# SWITCHER_V2.net
KiCad netlist of a schematic drawn in EAGLE
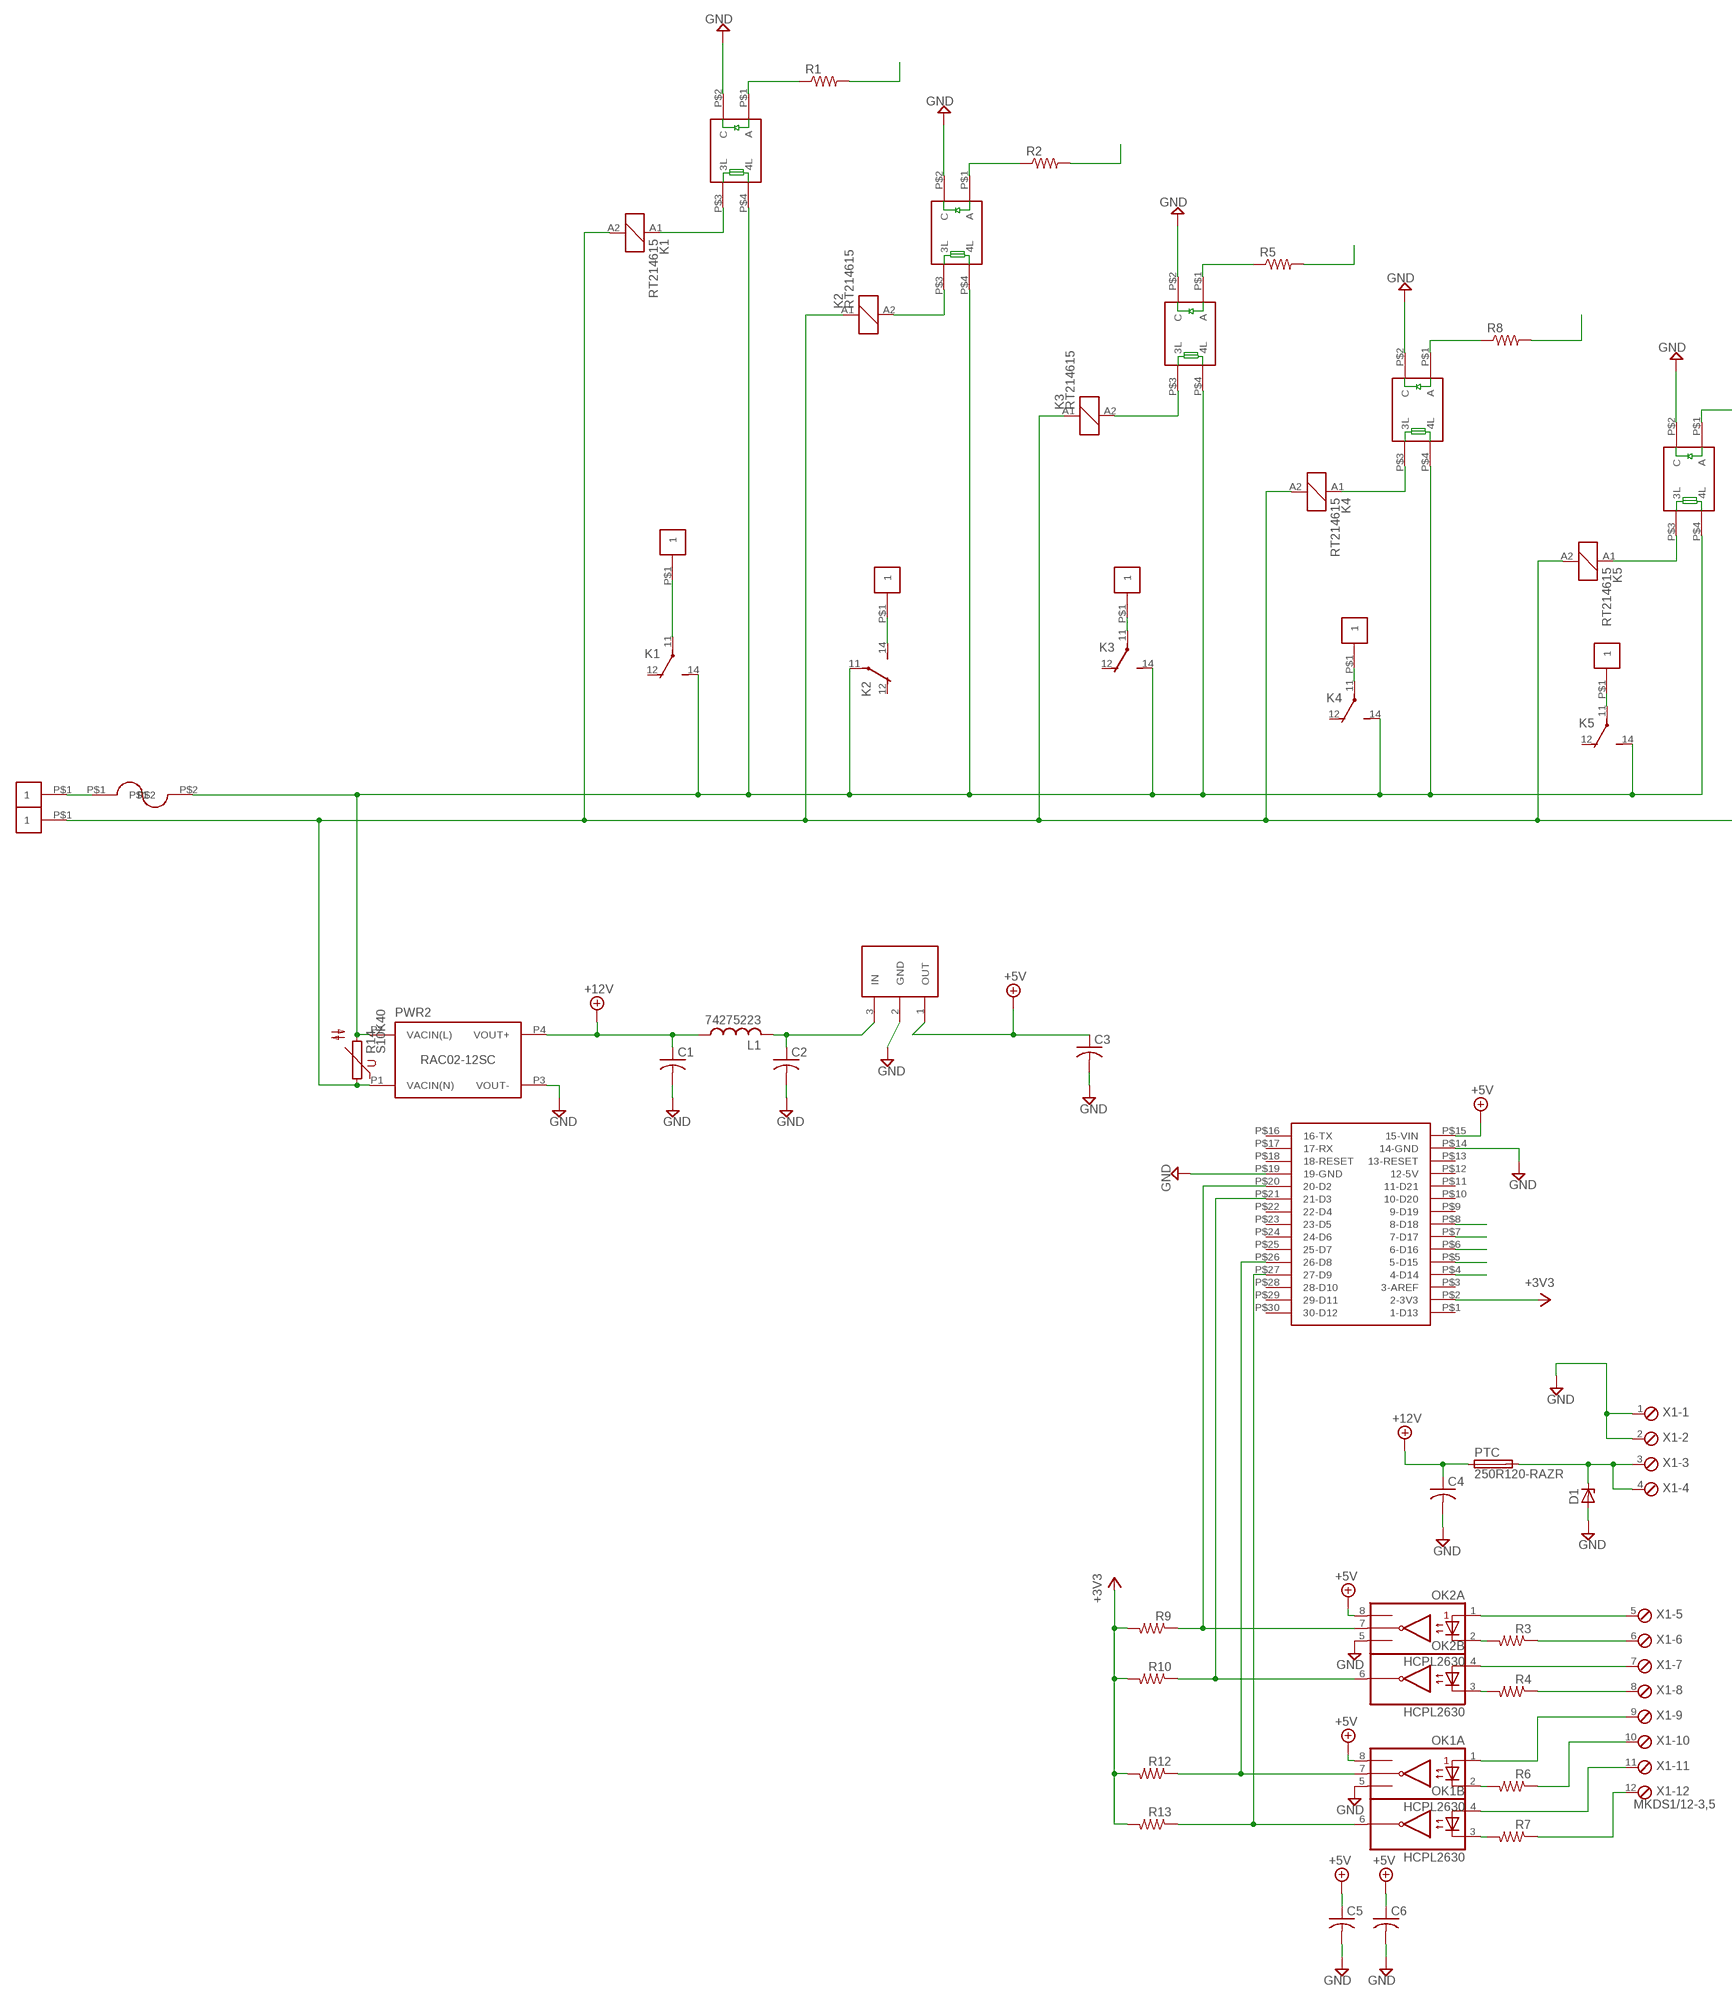
[diagram p0: schematic, sheet 1, part 1 of 2]
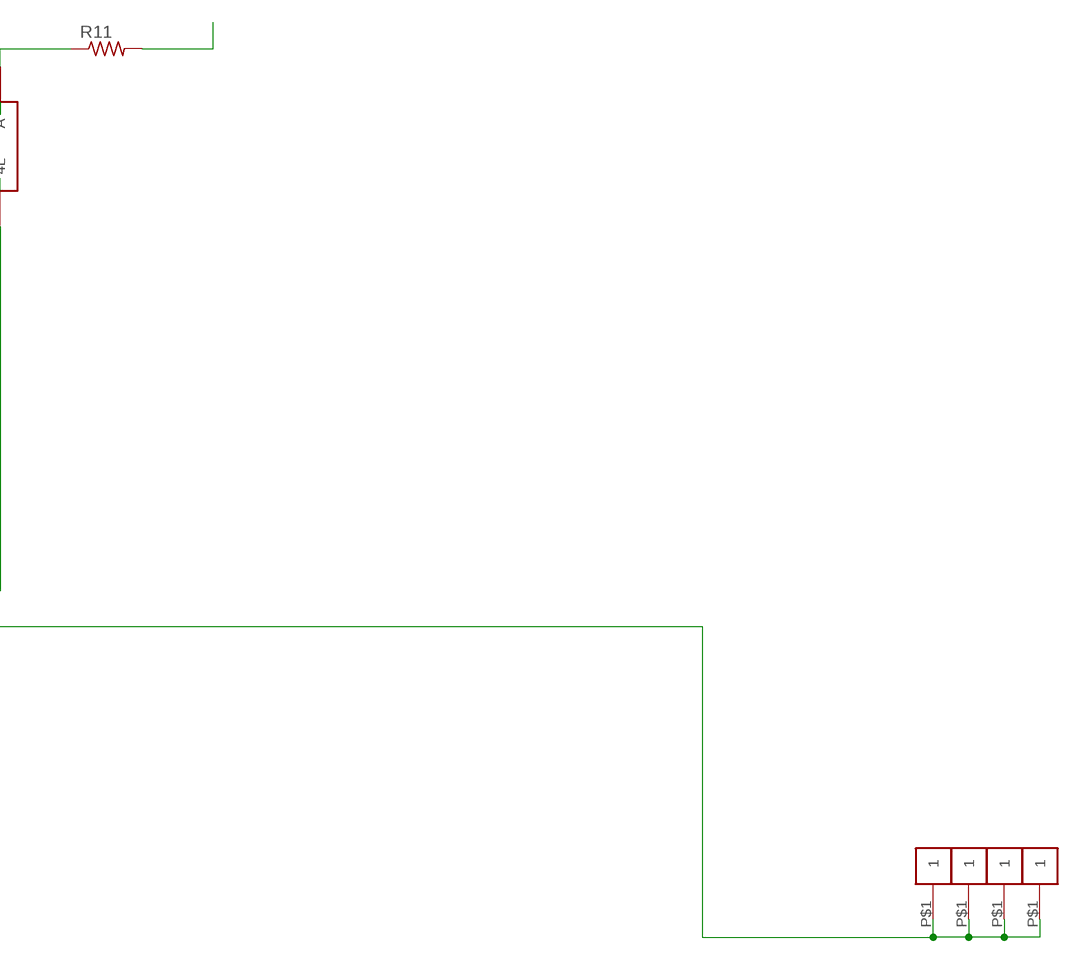
[diagram p1: schematic, sheet 1, part 2 of 2]

(export (version "E")
  (design (tool "Eeschema 10.0.6"))
  (components
    (comp (ref "C1")
      (value "C-US025-024X044")
      (footprint "eagle-import:C025-024X044")
      (libsource (lib "eagle-import") (part "C-US025-024X044"))
    )
    (comp (ref "C2")
      (value "C-US025-024X044")
      (footprint "eagle-import:C025-024X044")
      (libsource (lib "eagle-import") (part "C-US025-024X044"))
    )
    (comp (ref "C3")
      (value "C-US025-024X044")
      (footprint "eagle-import:C025-024X044")
      (libsource (lib "eagle-import") (part "C-US025-024X044"))
    )
    (comp (ref "C4")
      (value "C-US050-025X075")
      (footprint "eagle-import:C050-025X075")
      (libsource (lib "eagle-import") (part "C-US050-025X075"))
    )
    (comp (ref "C5")
      (value "C-US025-024X044")
      (footprint "eagle-import:C025-024X044")
      (libsource (lib "eagle-import") (part "C-US025-024X044"))
    )
    (comp (ref "C6")
      (value "C-US025-024X044")
      (footprint "eagle-import:C025-024X044")
      (libsource (lib "eagle-import") (part "C-US025-024X044"))
    )
    (comp (ref "D1")
      (value "ZENER-DIODEZD-5")
      (footprint "eagle-import:ZDIO-5")
      (libsource (lib "eagle-import") (part "ZENER-DIODEZD-5"))
    )
    (comp (ref "K1")
      (value "RT214615")
      (footprint "eagle-import:RT-C_O12A5")
      (fields (field (name "MF") "TYCO ELECTRONICS"))
      (libsource (lib "eagle-import") (part "RT?124615"))
    )
    (comp (ref "K2")
      (value "RT214615")
      (footprint "eagle-import:RT-C_O12A5")
      (fields (field (name "MF") "TYCO ELECTRONICS"))
      (libsource (lib "eagle-import") (part "RT?124615"))
    )
    (comp (ref "K3")
      (value "RT214615")
      (footprint "eagle-import:RT-C_O12A5")
      (fields (field (name "MF") "TYCO ELECTRONICS"))
      (libsource (lib "eagle-import") (part "RT?124615"))
    )
    (comp (ref "K4")
      (value "RT214615")
      (footprint "eagle-import:RT-C_O12A5")
      (fields (field (name "MF") "TYCO ELECTRONICS"))
      (libsource (lib "eagle-import") (part "RT?124615"))
    )
    (comp (ref "K5")
      (value "RT214615")
      (footprint "eagle-import:RT-C_O12A5")
      (fields (field (name "MF") "TYCO ELECTRONICS"))
      (libsource (lib "eagle-import") (part "RT?124615"))
    )
    (comp (ref "L1")
      (value "74275223")
      (footprint "eagle-import:6000-XXXX-RC")
      (libsource (lib "eagle-import") (part "L-US6000-XXX-RC"))
    )
    (comp (ref "OK1")
      (value "HCPL2630")
      (footprint "eagle-import:DIL08")
      (fields (field (name "MF") "AGILENT TECHNOLOGIES") (field (name "MPN") "HCPL-2630-000E"))
      (libsource (lib "eagle-import") (part "HCPL2630"))
    )
    (comp (ref "OK2")
      (value "HCPL2630")
      (footprint "eagle-import:DIL08")
      (fields (field (name "MF") "AGILENT TECHNOLOGIES") (field (name "MPN") "HCPL-2630-000E"))
      (libsource (lib "eagle-import") (part "HCPL2630"))
    )
    (comp (ref "PTC")
      (value "250R120-RAZR")
      (footprint "eagle-import:TE5")
      (libsource (lib "eagle-import") (part "TE5"))
    )
    (comp (ref "PWR2")
      (value "RAC02-12SC")
      (footprint "eagle-import:LOW_PROFILE_POWER_MODULE")
      (libsource (lib "eagle-import") (part "RACSC02-12"))
    )
    (comp (ref "R1")
      (value "R-US_0204/7")
      (footprint "eagle-import:0204_7")
      (libsource (lib "eagle-import") (part "R-US_0204/7"))
    )
    (comp (ref "R2")
      (value "R-US_0204/7")
      (footprint "eagle-import:0204_7")
      (libsource (lib "eagle-import") (part "R-US_0204/7"))
    )
    (comp (ref "R3")
      (value "R-US_0204/7")
      (footprint "eagle-import:0204_7")
      (libsource (lib "eagle-import") (part "R-US_0204/7"))
    )
    (comp (ref "R4")
      (value "R-US_0204/7")
      (footprint "eagle-import:0204_7")
      (libsource (lib "eagle-import") (part "R-US_0204/7"))
    )
    (comp (ref "R5")
      (value "R-US_0204/7")
      (footprint "eagle-import:0204_7")
      (libsource (lib "eagle-import") (part "R-US_0204/7"))
    )
    (comp (ref "R6")
      (value "R-US_0204/7")
      (footprint "eagle-import:0204_7")
      (libsource (lib "eagle-import") (part "R-US_0204/7"))
    )
    (comp (ref "R7")
      (value "R-US_0204/7")
      (footprint "eagle-import:0204_7")
      (libsource (lib "eagle-import") (part "R-US_0204/7"))
    )
    (comp (ref "R8")
      (value "R-US_0204/7")
      (footprint "eagle-import:0204_7")
      (libsource (lib "eagle-import") (part "R-US_0204/7"))
    )
    (comp (ref "R9")
      (value "R-US_0204/7")
      (footprint "eagle-import:0204_7")
      (libsource (lib "eagle-import") (part "R-US_0204/7"))
    )
    (comp (ref "R10")
      (value "R-US_0204/7")
      (footprint "eagle-import:0204_7")
      (libsource (lib "eagle-import") (part "R-US_0204/7"))
    )
    (comp (ref "R11")
      (value "R-US_0204/7")
      (footprint "eagle-import:0204_7")
      (libsource (lib "eagle-import") (part "R-US_0204/7"))
    )
    (comp (ref "R12")
      (value "R-US_0204/7")
      (footprint "eagle-import:0204_7")
      (libsource (lib "eagle-import") (part "R-US_0204/7"))
    )
    (comp (ref "R13")
      (value "R-US_0204/7")
      (footprint "eagle-import:0204_7")
      (libsource (lib "eagle-import") (part "R-US_0204/7"))
    )
    (comp (ref "R14")
      (value "S10K40")
      (footprint "eagle-import:S10K40")
      (libsource (lib "eagle-import") (part "S10K40"))
    )
    (comp (ref "U$1")
      (value "CPC1393")
      (footprint "eagle-import:CPC1393G")
      (libsource (lib "eagle-import") (part "CPC1393"))
    )
    (comp (ref "U$2")
      (value "089RIVET")
      (footprint "eagle-import:KEYSTONE33")
      (libsource (lib "eagle-import") (part "089RIVET"))
    )
    (comp (ref "U$3")
      (value "T9-818")
      (footprint "eagle-import:T9-818")
      (libsource (lib "eagle-import") (part "T9-818"))
    )
    (comp (ref "U$4")
      (value "CPC1393")
      (footprint "eagle-import:CPC1393G")
      (libsource (lib "eagle-import") (part "CPC1393"))
    )
    (comp (ref "U$5")
      (value "CPC1393")
      (footprint "eagle-import:CPC1393G")
      (libsource (lib "eagle-import") (part "CPC1393"))
    )
    (comp (ref "U$6")
      (value "CPC1393")
      (footprint "eagle-import:CPC1393G")
      (libsource (lib "eagle-import") (part "CPC1393"))
    )
    (comp (ref "U$7")
      (value "CPC1393")
      (footprint "eagle-import:CPC1393G")
      (libsource (lib "eagle-import") (part "CPC1393"))
    )
    (comp (ref "U$8")
      (value "TL750")
      (footprint "eagle-import:TO92-OVAL")
      (libsource (lib "eagle-import") (part "TL750"))
    )
    (comp (ref "U$9")
      (value "ARDUINO-NANO-EVERY")
      (footprint "eagle-import:ARDUINO-NANO-EVERY")
      (libsource (lib "eagle-import") (part "ARDUINO-NANO-EVERY"))
    )
    (comp (ref "U$11")
      (value "089RIVET")
      (footprint "eagle-import:KEYSTONE33")
      (libsource (lib "eagle-import") (part "089RIVET"))
    )
    (comp (ref "U$12")
      (value "089RIVET")
      (footprint "eagle-import:KEYSTONE33")
      (libsource (lib "eagle-import") (part "089RIVET"))
    )
    (comp (ref "U$13")
      (value "089RIVET")
      (footprint "eagle-import:KEYSTONE33")
      (libsource (lib "eagle-import") (part "089RIVET"))
    )
    (comp (ref "U$14")
      (value "089RIVET")
      (footprint "eagle-import:KEYSTONE33")
      (libsource (lib "eagle-import") (part "089RIVET"))
    )
    (comp (ref "U$21")
      (value "089RIVET")
      (footprint "eagle-import:KEYSTONE33")
      (libsource (lib "eagle-import") (part "089RIVET"))
    )
    (comp (ref "U$22")
      (value "089RIVET")
      (footprint "eagle-import:KEYSTONE33")
      (libsource (lib "eagle-import") (part "089RIVET"))
    )
    (comp (ref "U$25")
      (value "089RIVET")
      (footprint "eagle-import:KEYSTONE33")
      (libsource (lib "eagle-import") (part "089RIVET"))
    )
    (comp (ref "U$26")
      (value "089RIVET")
      (footprint "eagle-import:KEYSTONE33")
      (libsource (lib "eagle-import") (part "089RIVET"))
    )
    (comp (ref "U$27")
      (value "089RIVET")
      (footprint "eagle-import:KEYSTONE33")
      (libsource (lib "eagle-import") (part "089RIVET"))
    )
    (comp (ref "U$28")
      (value "089RIVET")
      (footprint "eagle-import:KEYSTONE33")
      (libsource (lib "eagle-import") (part "089RIVET"))
    )
    (comp (ref "X1")
      (value "MKDS1/12-3,5")
      (footprint "eagle-import:12POL350")
      (libsource (lib "eagle-import") (part "MKDS1/12-3,5"))
    )
  )
  (nets
    (net (code "1") (name "+3V3") (class "Default")
      (node (ref "R10") (pin "2") (pinfunction "2_2") (pintype "passive"))
      (node (ref "R12") (pin "2") (pinfunction "2_2") (pintype "passive"))
      (node (ref "R13") (pin "2") (pinfunction "2_2") (pintype "passive"))
      (node (ref "R9") (pin "2") (pinfunction "2_2") (pintype "passive"))
      (node (ref "U$9") (pin "P$2") (pinfunction "2-3V3_P$2") (pintype "bidirectional"))
    )
    (net (code "2") (name "+5V") (class "Default")
      (node (ref "C3") (pin "1") (pinfunction "1_1") (pintype "passive"))
      (node (ref "C5") (pin "1") (pinfunction "1_1") (pintype "passive"))
      (node (ref "C6") (pin "1") (pinfunction "1_1") (pintype "passive"))
      (node (ref "OK1") (pin "8") (pinfunction "VCC_8") (pintype "passive"))
      (node (ref "OK2") (pin "8") (pinfunction "VCC_8") (pintype "passive"))
      (node (ref "U$8") (pin "1") (pinfunction "OUT_1") (pintype "bidirectional"))
      (node (ref "U$9") (pin "P$15") (pinfunction "15-VIN_P$15") (pintype "bidirectional"))
    )
    (net (code "3") (name "+12V") (class "Default")
      (node (ref "C1") (pin "1") (pinfunction "1_1") (pintype "passive"))
      (node (ref "C4") (pin "1") (pinfunction "1_1") (pintype "passive"))
      (node (ref "L1") (pin "1") (pinfunction "1_1") (pintype "passive"))
      (node (ref "PTC") (pin "1") (pinfunction "1_1") (pintype "passive"))
      (node (ref "PWR2") (pin "P4") (pinfunction "VOUT+_P4") (pintype "power_in"))
    )
    (net (code "4") (name "/D14") (class "Default")
      (node (ref "R1") (pin "2") (pinfunction "2_2") (pintype "passive"))
      (node (ref "U$9") (pin "P$4") (pinfunction "4-D14_P$4") (pintype "bidirectional"))
    )
    (net (code "5") (name "/D15") (class "Default")
      (node (ref "R2") (pin "2") (pinfunction "2_2") (pintype "passive"))
      (node (ref "U$9") (pin "P$5") (pinfunction "5-D15_P$5") (pintype "bidirectional"))
    )
    (net (code "6") (name "/D16") (class "Default")
      (node (ref "R11") (pin "2") (pinfunction "2_2") (pintype "passive"))
      (node (ref "U$9") (pin "P$6") (pinfunction "6-D16_P$6") (pintype "bidirectional"))
    )
    (net (code "7") (name "/D17") (class "Default")
      (node (ref "R8") (pin "2") (pinfunction "2_2") (pintype "passive"))
      (node (ref "U$9") (pin "P$7") (pinfunction "7-D17_P$7") (pintype "bidirectional"))
    )
    (net (code "8") (name "/D18") (class "Default")
      (node (ref "R5") (pin "2") (pinfunction "2_2") (pintype "passive"))
      (node (ref "U$9") (pin "P$8") (pinfunction "8-D18_P$8") (pintype "bidirectional"))
    )
    (net (code "9") (name "GND") (class "Default")
      (node (ref "C1") (pin "2") (pinfunction "2_2") (pintype "passive"))
      (node (ref "C2") (pin "2") (pinfunction "2_2") (pintype "passive"))
      (node (ref "C3") (pin "2") (pinfunction "2_2") (pintype "passive"))
      (node (ref "C4") (pin "2") (pinfunction "2_2") (pintype "passive"))
      (node (ref "C5") (pin "2") (pinfunction "2_2") (pintype "passive"))
      (node (ref "C6") (pin "2") (pinfunction "2_2") (pintype "passive"))
      (node (ref "D1") (pin "A") (pinfunction "A_A") (pintype "passive"))
      (node (ref "OK1") (pin "5") (pinfunction "GND_5") (pintype "passive"))
      (node (ref "OK2") (pin "5") (pinfunction "GND_5") (pintype "passive"))
      (node (ref "PWR2") (pin "P3") (pinfunction "VOUT-_P3") (pintype "power_in"))
      (node (ref "U$1") (pin "P$2") (pinfunction "C_P$2") (pintype "bidirectional"))
      (node (ref "U$4") (pin "P$2") (pinfunction "C_P$2") (pintype "bidirectional"))
      (node (ref "U$5") (pin "P$2") (pinfunction "C_P$2") (pintype "bidirectional"))
      (node (ref "U$6") (pin "P$2") (pinfunction "C_P$2") (pintype "bidirectional"))
      (node (ref "U$7") (pin "P$2") (pinfunction "C_P$2") (pintype "bidirectional"))
      (node (ref "U$8") (pin "2") (pinfunction "GND_2") (pintype "bidirectional"))
      (node (ref "U$9") (pin "P$14") (pinfunction "14-GND_P$14") (pintype "bidirectional"))
      (node (ref "U$9") (pin "P$19") (pinfunction "19-GND_P$19") (pintype "bidirectional"))
      (node (ref "X1") (pin "1") (pinfunction "1_1") (pintype "passive"))
      (node (ref "X1") (pin "2") (pinfunction "1_2") (pintype "passive"))
    )
    (net (code "10") (name "Net-(K1A-1)") (class "Default")
      (node (ref "K1") (pin "A1") (pinfunction "1_A1") (pintype "passive"))
      (node (ref "U$1") (pin "P$3") (pinfunction "3L_P$3") (pintype "bidirectional"))
    )
    (net (code "11") (name "Net-(K1A-2)") (class "Default")
      (node (ref "K1") (pin "A2") (pinfunction "2_A2") (pintype "passive"))
      (node (ref "K2") (pin "A1") (pinfunction "1_A1") (pintype "passive"))
      (node (ref "K3") (pin "A1") (pinfunction "1_A1") (pintype "passive"))
      (node (ref "K4") (pin "A2") (pinfunction "2_A2") (pintype "passive"))
      (node (ref "K5") (pin "A2") (pinfunction "2_A2") (pintype "passive"))
      (node (ref "PWR2") (pin "P1") (pinfunction "VACIN(N)_P1") (pintype "power_in"))
      (node (ref "R14") (pin "1") (pinfunction "1_1") (pintype "passive"))
      (node (ref "U$11") (pin "P$1") (pinfunction "1_P$1") (pintype "bidirectional"))
      (node (ref "U$12") (pin "P$1") (pinfunction "1_P$1") (pintype "bidirectional"))
      (node (ref "U$13") (pin "P$1") (pinfunction "1_P$1") (pintype "bidirectional"))
      (node (ref "U$14") (pin "P$1") (pinfunction "1_P$1") (pintype "bidirectional"))
      (node (ref "U$22") (pin "P$1") (pinfunction "1_P$1") (pintype "bidirectional"))
    )
    (net (code "12") (name "Net-(K1B-P)") (class "Default")
      (node (ref "K1") (pin "11") (pinfunction "P_11") (pintype "passive"))
      (node (ref "U$21") (pin "P$1") (pinfunction "1_P$1") (pintype "bidirectional"))
    )
    (net (code "13") (name "Net-(K1B-S)") (class "Default")
      (node (ref "K1") (pin "14") (pinfunction "S_14") (pintype "passive"))
      (node (ref "K2") (pin "11") (pinfunction "P_11") (pintype "passive"))
      (node (ref "K3") (pin "14") (pinfunction "S_14") (pintype "passive"))
      (node (ref "K4") (pin "14") (pinfunction "S_14") (pintype "passive"))
      (node (ref "K5") (pin "14") (pinfunction "S_14") (pintype "passive"))
      (node (ref "PWR2") (pin "P2") (pinfunction "VACIN(L)_P2") (pintype "power_in"))
      (node (ref "R14") (pin "2") (pinfunction "2_2") (pintype "passive"))
      (node (ref "U$1") (pin "P$4") (pinfunction "4L_P$4") (pintype "bidirectional"))
      (node (ref "U$3") (pin "P$2") (pinfunction "P$2_P$2") (pintype "bidirectional"))
      (node (ref "U$4") (pin "P$4") (pinfunction "4L_P$4") (pintype "bidirectional"))
      (node (ref "U$5") (pin "P$4") (pinfunction "4L_P$4") (pintype "bidirectional"))
      (node (ref "U$6") (pin "P$4") (pinfunction "4L_P$4") (pintype "bidirectional"))
      (node (ref "U$7") (pin "P$4") (pinfunction "4L_P$4") (pintype "bidirectional"))
    )
    (net (code "14") (name "Net-(K2A-2)") (class "Default")
      (node (ref "K2") (pin "A2") (pinfunction "2_A2") (pintype "passive"))
      (node (ref "U$4") (pin "P$3") (pinfunction "3L_P$3") (pintype "bidirectional"))
    )
    (net (code "15") (name "Net-(K2B-S)") (class "Default")
      (node (ref "K2") (pin "14") (pinfunction "S_14") (pintype "passive"))
      (node (ref "U$25") (pin "P$1") (pinfunction "1_P$1") (pintype "bidirectional"))
    )
    (net (code "16") (name "Net-(K3A-2)") (class "Default")
      (node (ref "K3") (pin "A2") (pinfunction "2_A2") (pintype "passive"))
      (node (ref "U$5") (pin "P$3") (pinfunction "3L_P$3") (pintype "bidirectional"))
    )
    (net (code "17") (name "Net-(K3B-P)") (class "Default")
      (node (ref "K3") (pin "11") (pinfunction "P_11") (pintype "passive"))
      (node (ref "U$26") (pin "P$1") (pinfunction "1_P$1") (pintype "bidirectional"))
    )
    (net (code "18") (name "Net-(K4A-1)") (class "Default")
      (node (ref "K4") (pin "A1") (pinfunction "1_A1") (pintype "passive"))
      (node (ref "U$6") (pin "P$3") (pinfunction "3L_P$3") (pintype "bidirectional"))
    )
    (net (code "19") (name "Net-(K4B-P)") (class "Default")
      (node (ref "K4") (pin "11") (pinfunction "P_11") (pintype "passive"))
      (node (ref "U$27") (pin "P$1") (pinfunction "1_P$1") (pintype "bidirectional"))
    )
    (net (code "20") (name "Net-(K5A-1)") (class "Default")
      (node (ref "K5") (pin "A1") (pinfunction "1_A1") (pintype "passive"))
      (node (ref "U$7") (pin "P$3") (pinfunction "3L_P$3") (pintype "bidirectional"))
    )
    (net (code "21") (name "Net-(K5B-P)") (class "Default")
      (node (ref "K5") (pin "11") (pinfunction "P_11") (pintype "passive"))
      (node (ref "U$28") (pin "P$1") (pinfunction "1_P$1") (pintype "bidirectional"))
    )
    (net (code "22") (name "Net-(OK1A-A1)") (class "Default")
      (node (ref "OK1") (pin "1") (pinfunction "A1_1") (pintype "passive"))
      (node (ref "X1") (pin "9") (pinfunction "1_9") (pintype "passive"))
    )
    (net (code "23") (name "Net-(OK1A-C1)") (class "Default")
      (node (ref "OK1") (pin "2") (pinfunction "C1_2") (pintype "passive"))
      (node (ref "R6") (pin "2") (pinfunction "2_2") (pintype "passive"))
    )
    (net (code "24") (name "Net-(OK1A-VO1)") (class "Default")
      (node (ref "OK1") (pin "7") (pinfunction "VO1_7") (pintype "passive"))
      (node (ref "R12") (pin "1") (pinfunction "1_1") (pintype "passive"))
      (node (ref "U$9") (pin "P$26") (pinfunction "26-D8_P$26") (pintype "bidirectional"))
    )
    (net (code "25") (name "Net-(OK1B-A2)") (class "Default")
      (node (ref "OK1") (pin "4") (pinfunction "A2_4") (pintype "passive"))
      (node (ref "X1") (pin "11") (pinfunction "1_11") (pintype "passive"))
    )
    (net (code "26") (name "Net-(OK1B-C2)") (class "Default")
      (node (ref "OK1") (pin "3") (pinfunction "C2_3") (pintype "passive"))
      (node (ref "R7") (pin "2") (pinfunction "2_2") (pintype "passive"))
    )
    (net (code "27") (name "Net-(OK1B-VO2)") (class "Default")
      (node (ref "OK1") (pin "6") (pinfunction "VO2_6") (pintype "passive"))
      (node (ref "R13") (pin "1") (pinfunction "1_1") (pintype "passive"))
      (node (ref "U$9") (pin "P$27") (pinfunction "27-D9_P$27") (pintype "bidirectional"))
    )
    (net (code "28") (name "Net-(OK2A-A1)") (class "Default")
      (node (ref "OK2") (pin "1") (pinfunction "A1_1") (pintype "passive"))
      (node (ref "X1") (pin "5") (pinfunction "1_5") (pintype "passive"))
    )
    (net (code "29") (name "Net-(OK2A-C1)") (class "Default")
      (node (ref "OK2") (pin "2") (pinfunction "C1_2") (pintype "passive"))
      (node (ref "R3") (pin "2") (pinfunction "2_2") (pintype "passive"))
    )
    (net (code "30") (name "Net-(OK2A-VO1)") (class "Default")
      (node (ref "OK2") (pin "7") (pinfunction "VO1_7") (pintype "passive"))
      (node (ref "R9") (pin "1") (pinfunction "1_1") (pintype "passive"))
      (node (ref "U$9") (pin "P$20") (pinfunction "20-D2_P$20") (pintype "bidirectional"))
    )
    (net (code "31") (name "Net-(OK2B-A2)") (class "Default")
      (node (ref "OK2") (pin "4") (pinfunction "A2_4") (pintype "passive"))
      (node (ref "X1") (pin "7") (pinfunction "1_7") (pintype "passive"))
    )
    (net (code "32") (name "Net-(OK2B-C2)") (class "Default")
      (node (ref "OK2") (pin "3") (pinfunction "C2_3") (pintype "passive"))
      (node (ref "R4") (pin "2") (pinfunction "2_2") (pintype "passive"))
    )
    (net (code "33") (name "Net-(OK2B-VO2)") (class "Default")
      (node (ref "OK2") (pin "6") (pinfunction "VO2_6") (pintype "passive"))
      (node (ref "R10") (pin "1") (pinfunction "1_1") (pintype "passive"))
      (node (ref "U$9") (pin "P$21") (pinfunction "21-D3_P$21") (pintype "bidirectional"))
    )
    (net (code "34") (name "Net-(U$1-A)") (class "Default")
      (node (ref "R1") (pin "1") (pinfunction "1_1") (pintype "passive"))
      (node (ref "U$1") (pin "P$1") (pinfunction "A_P$1") (pintype "bidirectional"))
    )
    (net (code "35") (name "Net-(U$2-1)") (class "Default")
      (node (ref "U$2") (pin "P$1") (pinfunction "1_P$1") (pintype "bidirectional"))
      (node (ref "U$3") (pin "P$1") (pinfunction "P$1_P$1") (pintype "bidirectional"))
    )
    (net (code "36") (name "Net-(U$4-A)") (class "Default")
      (node (ref "R2") (pin "1") (pinfunction "1_1") (pintype "passive"))
      (node (ref "U$4") (pin "P$1") (pinfunction "A_P$1") (pintype "bidirectional"))
    )
    (net (code "37") (name "Net-(U$5-A)") (class "Default")
      (node (ref "R5") (pin "1") (pinfunction "1_1") (pintype "passive"))
      (node (ref "U$5") (pin "P$1") (pinfunction "A_P$1") (pintype "bidirectional"))
    )
    (net (code "38") (name "Net-(U$6-A)") (class "Default")
      (node (ref "R8") (pin "1") (pinfunction "1_1") (pintype "passive"))
      (node (ref "U$6") (pin "P$1") (pinfunction "A_P$1") (pintype "bidirectional"))
    )
    (net (code "39") (name "Net-(U$7-A)") (class "Default")
      (node (ref "R11") (pin "1") (pinfunction "1_1") (pintype "passive"))
      (node (ref "U$7") (pin "P$1") (pinfunction "A_P$1") (pintype "bidirectional"))
    )
    (net (code "40") (name "Net-(U$8-IN)") (class "Default")
      (node (ref "C2") (pin "1") (pinfunction "1_1") (pintype "passive"))
      (node (ref "L1") (pin "2") (pinfunction "2_2") (pintype "passive"))
      (node (ref "U$8") (pin "3") (pinfunction "IN_3") (pintype "bidirectional"))
    )
    (net (code "41") (name "Net-(X1B-1)") (class "Default")
      (node (ref "R6") (pin "1") (pinfunction "1_1") (pintype "passive"))
      (node (ref "X1") (pin "10") (pinfunction "1_10") (pintype "passive"))
    )
    (net (code "42") (name "Net-(X1D-1)") (class "Default")
      (node (ref "R7") (pin "1") (pinfunction "1_1") (pintype "passive"))
      (node (ref "X1") (pin "12") (pinfunction "1_12") (pintype "passive"))
    )
    (net (code "43") (name "Net-(X1F-1)") (class "Default")
      (node (ref "D1") (pin "C") (pinfunction "C_C") (pintype "passive"))
      (node (ref "PTC") (pin "2") (pinfunction "2_2") (pintype "passive"))
      (node (ref "X1") (pin "3") (pinfunction "1_3") (pintype "passive"))
      (node (ref "X1") (pin "4") (pinfunction "1_4") (pintype "passive"))
    )
    (net (code "44") (name "Net-(X1I-1)") (class "Default")
      (node (ref "R3") (pin "1") (pinfunction "1_1") (pintype "passive"))
      (node (ref "X1") (pin "6") (pinfunction "1_6") (pintype "passive"))
    )
    (net (code "45") (name "Net-(X1K-1)") (class "Default")
      (node (ref "R4") (pin "1") (pinfunction "1_1") (pintype "passive"))
      (node (ref "X1") (pin "8") (pinfunction "1_8") (pintype "passive"))
    )
    (net (code "46") (name "unconnected-(K1B-O-Pad12)") (class "Default")
      (node (ref "K1") (pin "12") (pinfunction "O_12") (pintype "passive"))
    )
    (net (code "47") (name "unconnected-(K2B-O-Pad12)") (class "Default")
      (node (ref "K2") (pin "12") (pinfunction "O_12") (pintype "passive"))
    )
    (net (code "48") (name "unconnected-(K3B-O-Pad12)") (class "Default")
      (node (ref "K3") (pin "12") (pinfunction "O_12") (pintype "passive"))
    )
    (net (code "49") (name "unconnected-(K4B-O-Pad12)") (class "Default")
      (node (ref "K4") (pin "12") (pinfunction "O_12") (pintype "passive"))
    )
    (net (code "50") (name "unconnected-(K5B-O-Pad12)") (class "Default")
      (node (ref "K5") (pin "12") (pinfunction "O_12") (pintype "passive"))
    )
    (net (code "51") (name "unconnected-(U$9-1-D13-PadP$1)") (class "Default")
      (node (ref "U$9") (pin "P$1") (pinfunction "1-D13_P$1") (pintype "bidirectional"))
    )
    (net (code "52") (name "unconnected-(U$9-3-AREF-PadP$3)") (class "Default")
      (node (ref "U$9") (pin "P$3") (pinfunction "3-AREF_P$3") (pintype "bidirectional"))
    )
    (net (code "53") (name "unconnected-(U$9-9-D19-PadP$9)") (class "Default")
      (node (ref "U$9") (pin "P$9") (pinfunction "9-D19_P$9") (pintype "bidirectional"))
    )
    (net (code "54") (name "unconnected-(U$9-10-D20-PadP$10)") (class "Default")
      (node (ref "U$9") (pin "P$10") (pinfunction "10-D20_P$10") (pintype "bidirectional"))
    )
    (net (code "55") (name "unconnected-(U$9-11-D21-PadP$11)") (class "Default")
      (node (ref "U$9") (pin "P$11") (pinfunction "11-D21_P$11") (pintype "bidirectional"))
    )
    (net (code "56") (name "unconnected-(U$9-12-5V-PadP$12)") (class "Default")
      (node (ref "U$9") (pin "P$12") (pinfunction "12-5V_P$12") (pintype "bidirectional"))
    )
    (net (code "57") (name "unconnected-(U$9-13-RESET-PadP$13)") (class "Default")
      (node (ref "U$9") (pin "P$13") (pinfunction "13-RESET_P$13") (pintype "bidirectional"))
    )
    (net (code "58") (name "unconnected-(U$9-16-TX-PadP$16)") (class "Default")
      (node (ref "U$9") (pin "P$16") (pinfunction "16-TX_P$16") (pintype "bidirectional"))
    )
    (net (code "59") (name "unconnected-(U$9-17-RX-PadP$17)") (class "Default")
      (node (ref "U$9") (pin "P$17") (pinfunction "17-RX_P$17") (pintype "bidirectional"))
    )
    (net (code "60") (name "unconnected-(U$9-18-RESET-PadP$18)") (class "Default")
      (node (ref "U$9") (pin "P$18") (pinfunction "18-RESET_P$18") (pintype "bidirectional"))
    )
    (net (code "61") (name "unconnected-(U$9-22-D4-PadP$22)") (class "Default")
      (node (ref "U$9") (pin "P$22") (pinfunction "22-D4_P$22") (pintype "bidirectional"))
    )
    (net (code "62") (name "unconnected-(U$9-23-D5-PadP$23)") (class "Default")
      (node (ref "U$9") (pin "P$23") (pinfunction "23-D5_P$23") (pintype "bidirectional"))
    )
    (net (code "63") (name "unconnected-(U$9-24-D6-PadP$24)") (class "Default")
      (node (ref "U$9") (pin "P$24") (pinfunction "24-D6_P$24") (pintype "bidirectional"))
    )
    (net (code "64") (name "unconnected-(U$9-25-D7-PadP$25)") (class "Default")
      (node (ref "U$9") (pin "P$25") (pinfunction "25-D7_P$25") (pintype "bidirectional"))
    )
    (net (code "65") (name "unconnected-(U$9-28-D10-PadP$28)") (class "Default")
      (node (ref "U$9") (pin "P$28") (pinfunction "28-D10_P$28") (pintype "bidirectional"))
    )
    (net (code "66") (name "unconnected-(U$9-29-D11-PadP$29)") (class "Default")
      (node (ref "U$9") (pin "P$29") (pinfunction "29-D11_P$29") (pintype "bidirectional"))
    )
    (net (code "67") (name "unconnected-(U$9-30-D12-PadP$30)") (class "Default")
      (node (ref "U$9") (pin "P$30") (pinfunction "30-D12_P$30") (pintype "bidirectional"))
    )
  )
)
